# dev_board.net
KiCad netlist of a schematic drawn in EAGLE
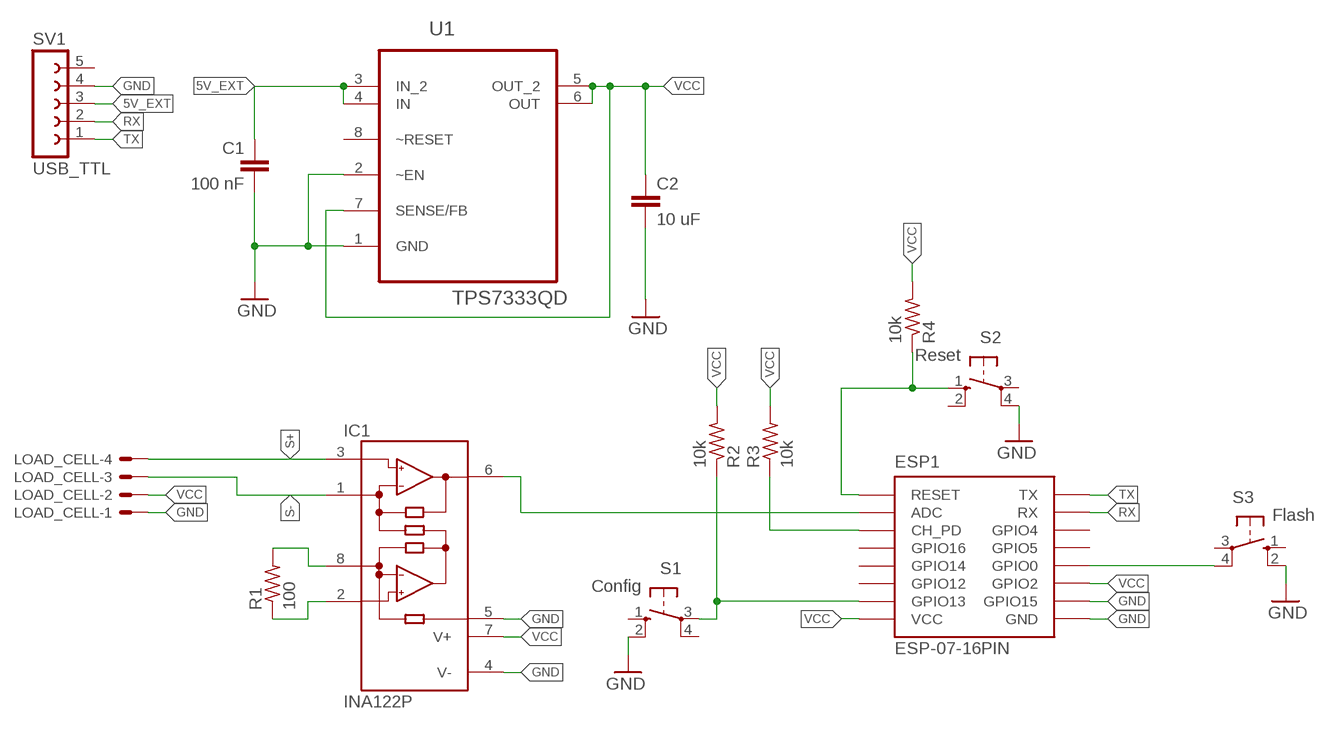
[diagram p0: schematic, sheet 1]

(export (version "E")
  (design (tool "Eeschema 10.0.6"))
  (components
    (comp (ref "C1")
      (value "100 nF")
      (footprint "eagle-import:C2.5-3")
      (libsource (lib "eagle-import") (part "C2,5-3"))
    )
    (comp (ref "C2")
      (value "10 uF")
      (footprint "eagle-import:C2.5-3")
      (libsource (lib "eagle-import") (part "C2,5-3"))
    )
    (comp (ref "ESP1")
      (value "ESP-07-16PIN")
      (footprint "eagle-import:ESP-07-16PIN")
      (libsource (lib "eagle-import") (part "ESP-07-16PIN"))
    )
    (comp (ref "IC1")
      (value "INA122P")
      (footprint "eagle-import:DIL08")
      (fields (field (name "MF") "TEXAS INSTRUMENTS"))
      (libsource (lib "eagle-import") (part "INA122P"))
    )
    (comp (ref "LOAD_CELL")
      (value "22-23-2041")
      (footprint "eagle-import:22-23-2041")
      (fields (field (name "MF") "MOLEX"))
      (libsource (lib "eagle-import") (part "22-23-2041"))
    )
    (comp (ref "R1")
      (value "100")
      (footprint "eagle-import:0204_5")
      (libsource (lib "eagle-import") (part "R-US_0204/5"))
    )
    (comp (ref "R2")
      (value "10k")
      (footprint "eagle-import:0204_5")
      (libsource (lib "eagle-import") (part "R-US_0204/5"))
    )
    (comp (ref "R3")
      (value "10k")
      (footprint "eagle-import:0204_5")
      (libsource (lib "eagle-import") (part "R-US_0204/5"))
    )
    (comp (ref "R4")
      (value "10k")
      (footprint "eagle-import:0204_5")
      (libsource (lib "eagle-import") (part "R-US_0204/5"))
    )
    (comp (ref "S1")
      (value "Config")
      (footprint "eagle-import:B3F-10XX")
      (fields (field (name "MPN") "B3F-1000"))
      (libsource (lib "eagle-import") (part "10-XX"))
    )
    (comp (ref "S2")
      (value "Reset")
      (footprint "eagle-import:B3F-10XX")
      (fields (field (name "MPN") "B3F-1000"))
      (libsource (lib "eagle-import") (part "10-XX"))
    )
    (comp (ref "S3")
      (value "Flash")
      (footprint "eagle-import:B3F-10XX")
      (fields (field (name "MPN") "B3F-1000"))
      (libsource (lib "eagle-import") (part "10-XX"))
    )
    (comp (ref "SV1")
      (value "USB_TTL")
      (footprint "eagle-import:FE05W")
      (libsource (lib "eagle-import") (part "FE05W"))
    )
    (comp (ref "U1")
      (value "TPS7333QD")
      (footprint "eagle-import:SOIC127P600X175-8N")
      (libsource (lib "eagle-import") (part "TPS7333QD"))
    )
  )
  (nets
    (net (code "1") (name "5V_EXT") (class "Default")
      (node (ref "C1") (pin "1") (pinfunction "1_1") (pintype "passive"))
      (node (ref "SV1") (pin "3") (pinfunction "3_3") (pintype "passive"))
      (node (ref "U1") (pin "3") (pinfunction "IN_2_3") (pintype "input"))
      (node (ref "U1") (pin "4") (pinfunction "IN_4") (pintype "input"))
    )
    (net (code "2") (name "GND") (class "Default")
      (node (ref "C1") (pin "2") (pinfunction "2_2") (pintype "passive"))
      (node (ref "C2") (pin "2") (pinfunction "2_2") (pintype "passive"))
      (node (ref "ESP1") (pin "GND") (pinfunction "GND_GND") (pintype "bidirectional"))
      (node (ref "ESP1") (pin "GPIO15") (pinfunction "GPIO15_GPIO15") (pintype "bidirectional"))
      (node (ref "IC1") (pin "4") (pinfunction "V-_4") (pintype "power_in"))
      (node (ref "IC1") (pin "5") (pinfunction "REF_5") (pintype "passive"))
      (node (ref "LOAD_CELL") (pin "1") (pinfunction "S_1") (pintype "passive"))
      (node (ref "S1") (pin "2") (pinfunction "S1_2") (pintype "passive"))
      (node (ref "S2") (pin "4") (pinfunction "P1_4") (pintype "passive"))
      (node (ref "S3") (pin "2") (pinfunction "S1_2") (pintype "passive"))
      (node (ref "SV1") (pin "4") (pinfunction "4_4") (pintype "passive"))
      (node (ref "U1") (pin "1") (pinfunction "GND_1") (pintype "passive"))
      (node (ref "U1") (pin "2") (pinfunction "~{EN}_2") (pintype "input"))
    )
    (net (code "3") (name "Net-(ESP1-PadCH_PD)") (class "Default")
      (node (ref "ESP1") (pin "CH_PD") (pinfunction "CH_PD_CH_PD") (pintype "bidirectional"))
      (node (ref "R3") (pin "1") (pinfunction "1_1") (pintype "passive"))
    )
    (net (code "4") (name "Net-(ESP1-RESET)") (class "Default")
      (node (ref "ESP1") (pin "REST") (pinfunction "RESET_REST") (pintype "bidirectional"))
      (node (ref "R4") (pin "1") (pinfunction "1_1") (pintype "passive"))
      (node (ref "S2") (pin "1") (pinfunction "S_1") (pintype "passive"))
    )
    (net (code "5") (name "Net-(IC1--IN)") (class "Default")
      (node (ref "IC1") (pin "2") (pinfunction "-IN_2") (pintype "input"))
      (node (ref "R1") (pin "1") (pinfunction "1_1") (pintype "passive"))
    )
    (net (code "6") (name "Net-(IC1-OUT)") (class "Default")
      (node (ref "ESP1") (pin "ADC") (pinfunction "ADC_ADC") (pintype "bidirectional"))
      (node (ref "IC1") (pin "6") (pinfunction "OUT_6") (pintype "output"))
    )
    (net (code "7") (name "Net-(IC1-RG-Pad8)") (class "Default")
      (node (ref "IC1") (pin "8") (pinfunction "RG_8") (pintype "passive"))
      (node (ref "R1") (pin "2") (pinfunction "2_2") (pintype "passive"))
    )
    (net (code "8") (name "Net-(S1-P)") (class "Default")
      (node (ref "ESP1") (pin "GPIO13") (pinfunction "GPIO13_GPIO13") (pintype "bidirectional"))
      (node (ref "R2") (pin "1") (pinfunction "1_1") (pintype "passive"))
      (node (ref "S1") (pin "3") (pinfunction "P_3") (pintype "passive"))
    )
    (net (code "9") (name "Net-(S3-P1)") (class "Default")
      (node (ref "ESP1") (pin "GPIO0") (pinfunction "GPIO0_GPIO0") (pintype "bidirectional"))
      (node (ref "S3") (pin "4") (pinfunction "P1_4") (pintype "passive"))
    )
    (net (code "10") (name "RX") (class "Default")
      (node (ref "ESP1") (pin "RX") (pinfunction "RX_RX") (pintype "bidirectional"))
      (node (ref "SV1") (pin "2") (pinfunction "2_2") (pintype "passive"))
    )
    (net (code "11") (name "S+") (class "Default")
      (node (ref "IC1") (pin "3") (pinfunction "+IN_3") (pintype "input"))
      (node (ref "LOAD_CELL") (pin "4") (pinfunction "S_4") (pintype "passive"))
    )
    (net (code "12") (name "S-") (class "Default")
      (node (ref "IC1") (pin "1") (pinfunction "RG_1") (pintype "passive"))
      (node (ref "LOAD_CELL") (pin "3") (pinfunction "S_3") (pintype "passive"))
    )
    (net (code "13") (name "TX") (class "Default")
      (node (ref "ESP1") (pin "TX") (pinfunction "TX_TX") (pintype "bidirectional"))
      (node (ref "SV1") (pin "1") (pinfunction "1_1") (pintype "passive"))
    )
    (net (code "14") (name "VCC") (class "Default")
      (node (ref "C2") (pin "1") (pinfunction "1_1") (pintype "passive"))
      (node (ref "ESP1") (pin "GPIO2") (pinfunction "GPIO2_GPIO2") (pintype "bidirectional"))
      (node (ref "ESP1") (pin "VCC") (pinfunction "VCC_VCC") (pintype "bidirectional"))
      (node (ref "IC1") (pin "7") (pinfunction "V+_7") (pintype "power_in"))
      (node (ref "LOAD_CELL") (pin "2") (pinfunction "S_2") (pintype "passive"))
      (node (ref "R2") (pin "2") (pinfunction "2_2") (pintype "passive"))
      (node (ref "R3") (pin "2") (pinfunction "2_2") (pintype "passive"))
      (node (ref "R4") (pin "2") (pinfunction "2_2") (pintype "passive"))
      (node (ref "U1") (pin "5") (pinfunction "OUT_2_5") (pintype "output"))
      (node (ref "U1") (pin "6") (pinfunction "OUT_6") (pintype "output"))
      (node (ref "U1") (pin "7") (pinfunction "SENSE/FB_7") (pintype "input"))
    )
    (net (code "15") (name "unconnected-(ESP1-PadGPIO4)") (class "Default")
      (node (ref "ESP1") (pin "GPIO4") (pinfunction "GPIO4_GPIO4") (pintype "bidirectional"))
    )
    (net (code "16") (name "unconnected-(ESP1-PadGPIO5)") (class "Default")
      (node (ref "ESP1") (pin "GPIO5") (pinfunction "GPIO5_GPIO5") (pintype "bidirectional"))
    )
    (net (code "17") (name "unconnected-(ESP1-PadGPIO12)") (class "Default")
      (node (ref "ESP1") (pin "GPIO12") (pinfunction "GPIO12_GPIO12") (pintype "bidirectional"))
    )
    (net (code "18") (name "unconnected-(ESP1-PadGPIO14)") (class "Default")
      (node (ref "ESP1") (pin "GPIO14") (pinfunction "GPIO14_GPIO14") (pintype "bidirectional"))
    )
    (net (code "19") (name "unconnected-(ESP1-PadGPIO16)") (class "Default")
      (node (ref "ESP1") (pin "GPIO16") (pinfunction "GPIO16_GPIO16") (pintype "bidirectional"))
    )
    (net (code "20") (name "unconnected-(S1-P1-Pad4)") (class "Default")
      (node (ref "S1") (pin "4") (pinfunction "P1_4") (pintype "passive"))
    )
    (net (code "21") (name "unconnected-(S1-S-Pad1)") (class "Default")
      (node (ref "S1") (pin "1") (pinfunction "S_1") (pintype "passive"))
    )
    (net (code "22") (name "unconnected-(S2-P-Pad3)") (class "Default")
      (node (ref "S2") (pin "3") (pinfunction "P_3") (pintype "passive"))
    )
    (net (code "23") (name "unconnected-(S2-S1-Pad2)") (class "Default")
      (node (ref "S2") (pin "2") (pinfunction "S1_2") (pintype "passive"))
    )
    (net (code "24") (name "unconnected-(S3-P-Pad3)") (class "Default")
      (node (ref "S3") (pin "3") (pinfunction "P_3") (pintype "passive"))
    )
    (net (code "25") (name "unconnected-(S3-S-Pad1)") (class "Default")
      (node (ref "S3") (pin "1") (pinfunction "S_1") (pintype "passive"))
    )
    (net (code "26") (name "unconnected-(SV1-Pad5)") (class "Default")
      (node (ref "SV1") (pin "5") (pinfunction "5_5") (pintype "passive"))
    )
    (net (code "27") (name "unconnected-(U1-~{RESET}-Pad8)") (class "Default")
      (node (ref "U1") (pin "8") (pinfunction "~{RESET}_8") (pintype "passive"))
    )
  )
)
